# connectors.net
KiCad netlist of a schematic drawn in Altium Designer
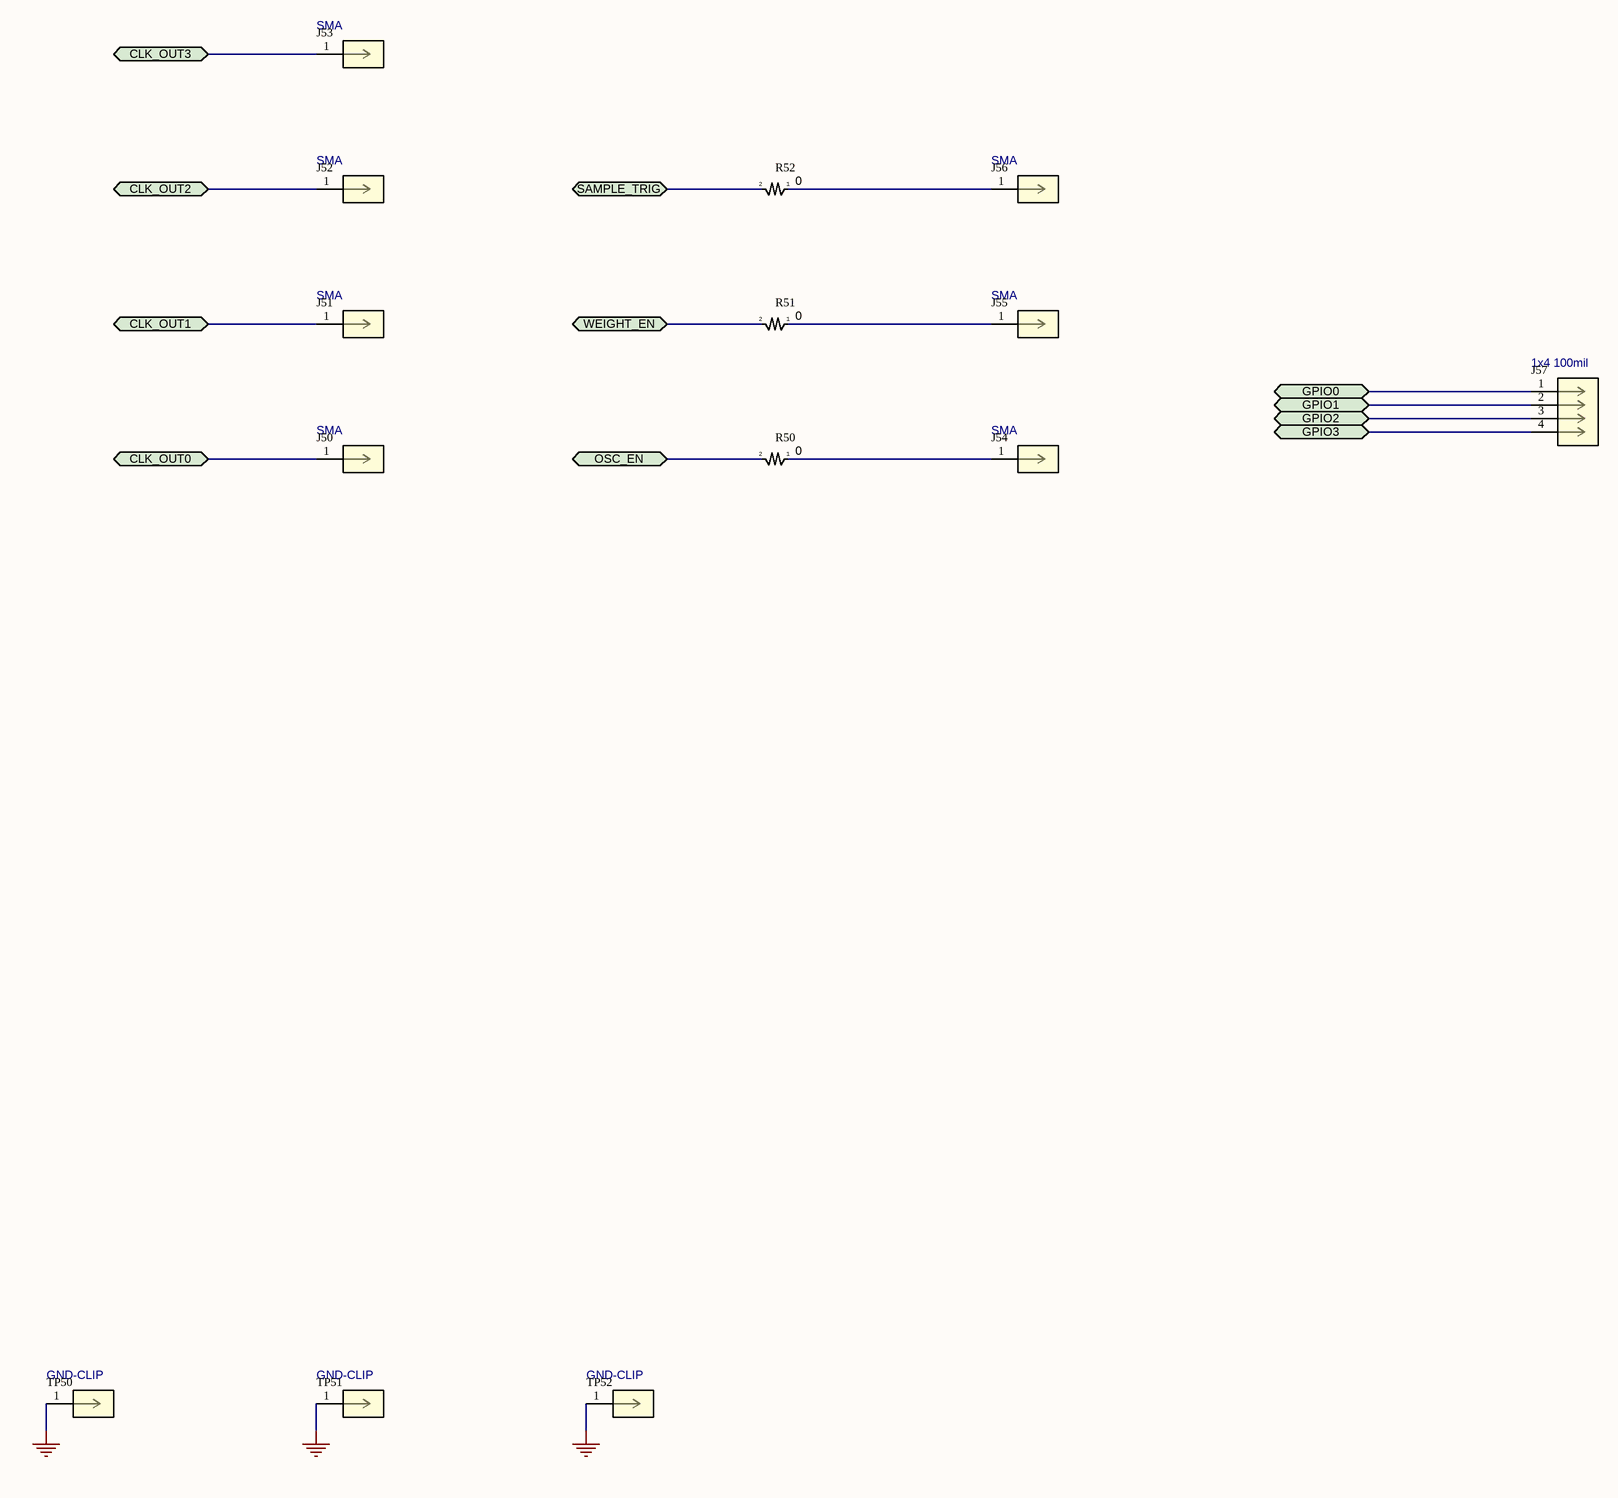
[diagram p0: connectors.SchDoc]

(export (version "E")
  (design (tool "Eeschema 10.0.6"))
  (components
    (comp (ref "J50")
      (value "SMA")
      (description "Description")
      (fields
        (field (name "MANUFACTURER_PART_NUMBER") "HRM(G)-300-467B-1")
        (field (name "COPYRIGHT") "Copyright (C) 2026 Ultra Librarian. All rights reserved.")
      )
      (libsource (lib "parts") (part "HRMG-300-467B-1"))
    )
    (comp (ref "J51")
      (value "SMA")
      (description "Description")
      (fields
        (field (name "MANUFACTURER_PART_NUMBER") "HRM(G)-300-467B-1")
        (field (name "COPYRIGHT") "Copyright (C) 2026 Ultra Librarian. All rights reserved.")
      )
      (libsource (lib "parts") (part "HRMG-300-467B-1"))
    )
    (comp (ref "J52")
      (value "SMA")
      (description "Description")
      (fields
        (field (name "MANUFACTURER_PART_NUMBER") "HRM(G)-300-467B-1")
        (field (name "COPYRIGHT") "Copyright (C) 2026 Ultra Librarian. All rights reserved.")
      )
      (libsource (lib "parts") (part "HRMG-300-467B-1"))
    )
    (comp (ref "J53")
      (value "SMA")
      (description "Description")
      (fields
        (field (name "MANUFACTURER_PART_NUMBER") "HRM(G)-300-467B-1")
        (field (name "COPYRIGHT") "Copyright (C) 2026 Ultra Librarian. All rights reserved.")
      )
      (libsource (lib "parts") (part "HRMG-300-467B-1"))
    )
    (comp (ref "J54")
      (value "SMA")
      (description "Description")
      (fields
        (field (name "MANUFACTURER_PART_NUMBER") "HRM(G)-300-467B-1")
        (field (name "COPYRIGHT") "Copyright (C) 2026 Ultra Librarian. All rights reserved.")
      )
      (libsource (lib "parts") (part "HRMG-300-467B-1"))
    )
    (comp (ref "J55")
      (value "SMA")
      (description "Description")
      (fields
        (field (name "MANUFACTURER_PART_NUMBER") "HRM(G)-300-467B-1")
        (field (name "COPYRIGHT") "Copyright (C) 2026 Ultra Librarian. All rights reserved.")
      )
      (libsource (lib "parts") (part "HRMG-300-467B-1"))
    )
    (comp (ref "J56")
      (value "SMA")
      (description "Description")
      (fields
        (field (name "MANUFACTURER_PART_NUMBER") "HRM(G)-300-467B-1")
        (field (name "COPYRIGHT") "Copyright (C) 2026 Ultra Librarian. All rights reserved.")
      )
      (libsource (lib "parts") (part "HRMG-300-467B-1"))
    )
    (comp (ref "J57")
      (value "1x4 100mil")
      (description "No Description Available")
      (fields
        (field (name "MANUFACTURER_PART_NUMBER") "TSW-104-05-G-S")
        (field (name "COPYRIGHT") "Copyright (C) 2026 Ultra Librarian. All rights reserved.")
      )
      (libsource (lib "parts") (part "TSW-104-05-G-S"))
    )
    (comp (ref "R50")
      (value "0")
      (description "D10/CRCW0402 0R0 ET7 e3")
      (fields (field (name "MANUFACTURER_PART_NUMBER") "CRCW04020000Z0ED"))
      (libsource (lib "parts") (part "CRCW04020000Z0ED"))
    )
    (comp (ref "R51")
      (value "0")
      (description "D10/CRCW0402 0R0 ET7 e3")
      (fields (field (name "MANUFACTURER_PART_NUMBER") "CRCW04020000Z0ED"))
      (libsource (lib "parts") (part "CRCW04020000Z0ED"))
    )
    (comp (ref "R52")
      (value "0")
      (description "D10/CRCW0402 0R0 ET7 e3")
      (fields (field (name "MANUFACTURER_PART_NUMBER") "CRCW04020000Z0ED"))
      (libsource (lib "parts") (part "CRCW04020000Z0ED"))
    )
    (comp (ref "TP50")
      (value "GND-CLIP")
      (fields
        (field (name "MANUFACTURER_PART_NUMBER") "5011")
        (field (name "COPYRIGHT") "Copyright (C) 2026 Ultra Librarian. All rights reserved.")
      )
      (libsource (lib "parts") (part "5011"))
    )
    (comp (ref "TP51")
      (value "GND-CLIP")
      (fields
        (field (name "MANUFACTURER_PART_NUMBER") "5011")
        (field (name "COPYRIGHT") "Copyright (C) 2026 Ultra Librarian. All rights reserved.")
      )
      (libsource (lib "parts") (part "5011"))
    )
    (comp (ref "TP52")
      (value "GND-CLIP")
      (fields
        (field (name "MANUFACTURER_PART_NUMBER") "5011")
        (field (name "COPYRIGHT") "Copyright (C) 2026 Ultra Librarian. All rights reserved.")
      )
      (libsource (lib "parts") (part "5011"))
    )
  )
  (nets
    (net (code "1") (name "/CLK_OUT0") (class "Default")
      (node (ref "J50") (pin "1") (pinfunction "1_1") (pintype "passive"))
    )
    (net (code "2") (name "/CLK_OUT1") (class "Default")
      (node (ref "J51") (pin "1") (pinfunction "1_1") (pintype "passive"))
    )
    (net (code "3") (name "/CLK_OUT2") (class "Default")
      (node (ref "J52") (pin "1") (pinfunction "1_1") (pintype "passive"))
    )
    (net (code "4") (name "/CLK_OUT3") (class "Default")
      (node (ref "J53") (pin "1") (pinfunction "1_1") (pintype "passive"))
    )
    (net (code "5") (name "/GPIO0") (class "Default")
      (node (ref "J57") (pin "1") (pinfunction "1_1") (pintype "passive"))
    )
    (net (code "6") (name "/GPIO1") (class "Default")
      (node (ref "J57") (pin "2") (pinfunction "2_2") (pintype "passive"))
    )
    (net (code "7") (name "/GPIO2") (class "Default")
      (node (ref "J57") (pin "3") (pinfunction "3_3") (pintype "passive"))
    )
    (net (code "8") (name "/GPIO3") (class "Default")
      (node (ref "J57") (pin "4") (pinfunction "4_4") (pintype "passive"))
    )
    (net (code "9") (name "/OSC_EN") (class "Default") (node (ref "R50") (pin "2") (pintype "passive")))
    (net (code "10") (name "/SAMPLE_TRIG") (class "Default") (node (ref "R52") (pin "2") (pintype "passive")))
    (net (code "11") (name "/WEIGHT_EN") (class "Default") (node (ref "R51") (pin "2") (pintype "passive")))
    (net (code "12") (name "GND") (class "Default")
      (node (ref "TP50") (pin "1") (pinfunction "1_1") (pintype "passive"))
      (node (ref "TP51") (pin "1") (pinfunction "1_1") (pintype "passive"))
      (node (ref "TP52") (pin "1") (pinfunction "1_1") (pintype "passive"))
    )
    (net (code "13") (name "Net-(J54-Pad1)") (class "Default")
      (node (ref "J54") (pin "1") (pinfunction "1_1") (pintype "passive"))
      (node (ref "R50") (pin "1") (pintype "passive"))
    )
    (net (code "14") (name "Net-(J55-Pad1)") (class "Default")
      (node (ref "J55") (pin "1") (pinfunction "1_1") (pintype "passive"))
      (node (ref "R51") (pin "1") (pintype "passive"))
    )
    (net (code "15") (name "Net-(J56-Pad1)") (class "Default")
      (node (ref "J56") (pin "1") (pinfunction "1_1") (pintype "passive"))
      (node (ref "R52") (pin "1") (pintype "passive"))
    )
  )
)
